# ShiftregisterTeil2.net
KiCad netlist of a schematic drawn in Altium Designer
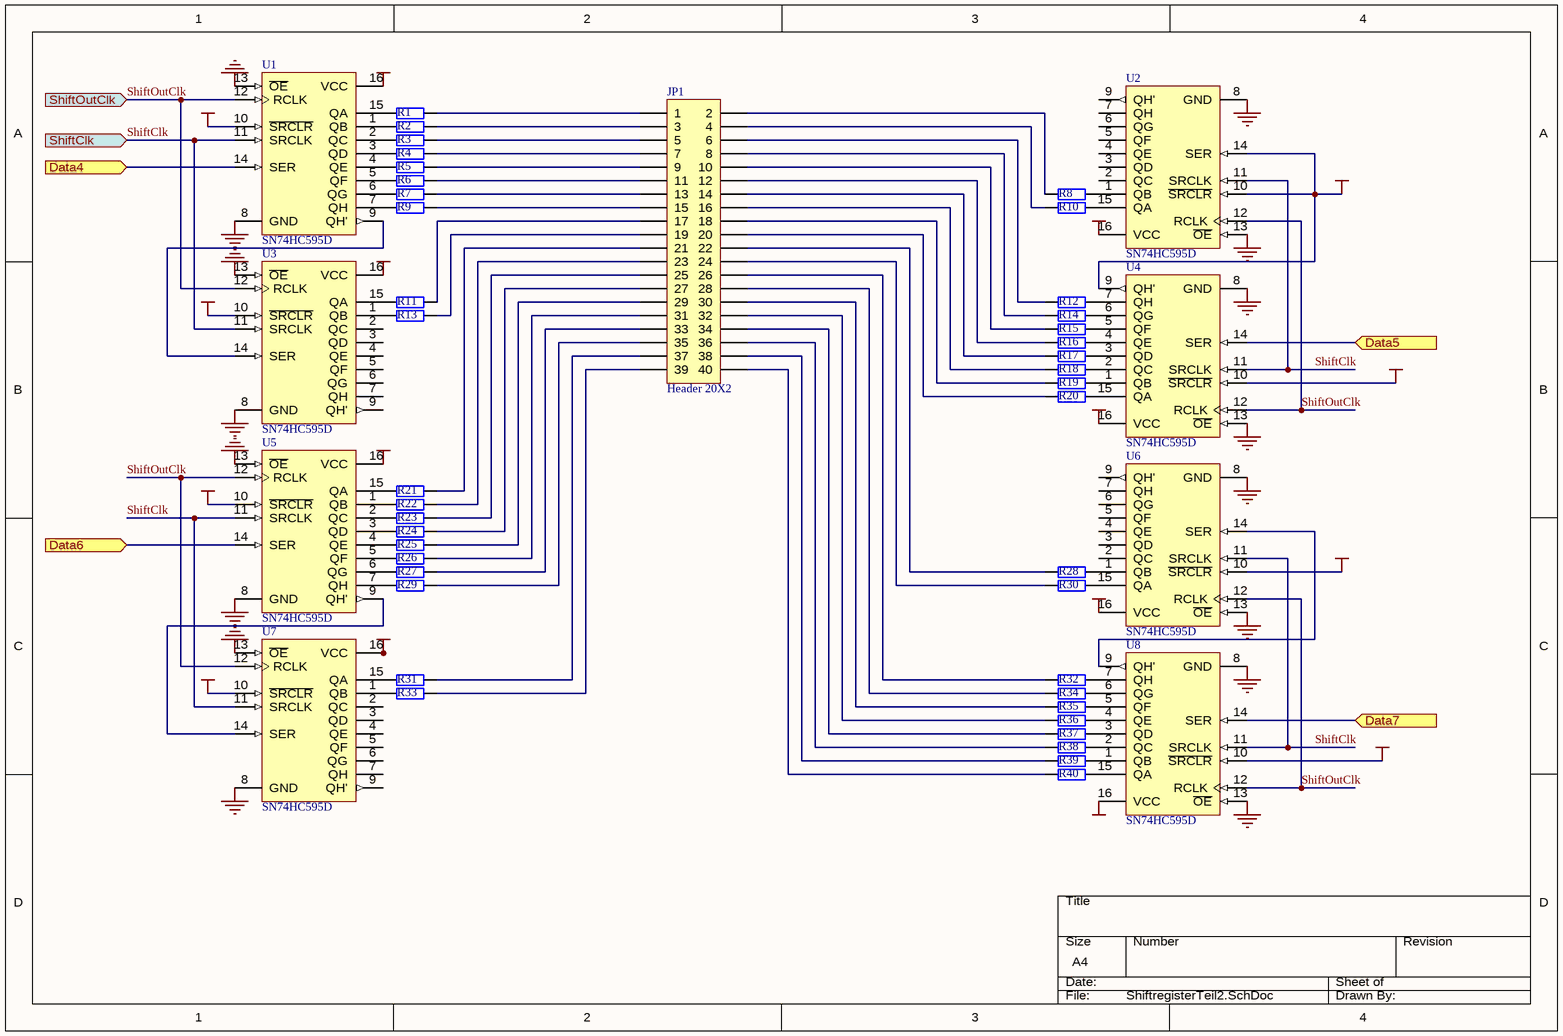
[diagram p0: ShiftregisterTeil2.SchDoc]

(export (version "E")
  (design (tool "Eeschema 10.0.6"))
  (components
    (comp (ref "JP1")
      (value "Header 20X2")
      (footprint "HDR2X20")
      (description "Header, 20-Pin, Dual row")
      (fields (field (name "PUBLISHER") "Altium Limited"))
      (libsource (lib "Miscellaneous Connectors") (part "Header 20X2"))
    )
    (comp (ref "R1")
      (value "~")
      (footprint "AXIAL-0.4")
      (description "Resistor")
      (fields (field (name "PUBLISHER") "Altium Limited"))
      (libsource (lib "Miscellaneous Devices") (part "Res2"))
    )
    (comp (ref "R2")
      (value "~")
      (footprint "AXIAL-0.4")
      (description "Resistor")
      (fields (field (name "PUBLISHER") "Altium Limited"))
      (libsource (lib "Miscellaneous Devices") (part "Res2"))
    )
    (comp (ref "R3")
      (value "~")
      (footprint "AXIAL-0.4")
      (description "Resistor")
      (fields (field (name "PUBLISHER") "Altium Limited"))
      (libsource (lib "Miscellaneous Devices") (part "Res2"))
    )
    (comp (ref "R4")
      (value "~")
      (footprint "AXIAL-0.4")
      (description "Resistor")
      (fields (field (name "PUBLISHER") "Altium Limited"))
      (libsource (lib "Miscellaneous Devices") (part "Res2"))
    )
    (comp (ref "R5")
      (value "~")
      (footprint "AXIAL-0.4")
      (description "Resistor")
      (fields (field (name "PUBLISHER") "Altium Limited"))
      (libsource (lib "Miscellaneous Devices") (part "Res2"))
    )
    (comp (ref "R6")
      (value "~")
      (footprint "AXIAL-0.4")
      (description "Resistor")
      (fields (field (name "PUBLISHER") "Altium Limited"))
      (libsource (lib "Miscellaneous Devices") (part "Res2"))
    )
    (comp (ref "R7")
      (value "~")
      (footprint "AXIAL-0.4")
      (description "Resistor")
      (fields (field (name "PUBLISHER") "Altium Limited"))
      (libsource (lib "Miscellaneous Devices") (part "Res2"))
    )
    (comp (ref "R8")
      (value "~")
      (footprint "AXIAL-0.4")
      (description "Resistor")
      (fields (field (name "PUBLISHER") "Altium Limited"))
      (libsource (lib "") (part "Res2_1"))
    )
    (comp (ref "R9")
      (value "~")
      (footprint "AXIAL-0.4")
      (description "Resistor")
      (fields (field (name "PUBLISHER") "Altium Limited"))
      (libsource (lib "Miscellaneous Devices") (part "Res2"))
    )
    (comp (ref "R10")
      (value "~")
      (footprint "AXIAL-0.4")
      (description "Resistor")
      (fields (field (name "PUBLISHER") "Altium Limited"))
      (libsource (lib "") (part "Res2_1"))
    )
    (comp (ref "R11")
      (value "~")
      (footprint "AXIAL-0.4")
      (description "Resistor")
      (fields (field (name "PUBLISHER") "Altium Limited"))
      (libsource (lib "Miscellaneous Devices") (part "Res2"))
    )
    (comp (ref "R12")
      (value "~")
      (footprint "AXIAL-0.4")
      (description "Resistor")
      (fields (field (name "PUBLISHER") "Altium Limited"))
      (libsource (lib "") (part "Res2_1"))
    )
    (comp (ref "R13")
      (value "~")
      (footprint "AXIAL-0.4")
      (description "Resistor")
      (fields (field (name "PUBLISHER") "Altium Limited"))
      (libsource (lib "Miscellaneous Devices") (part "Res2"))
    )
    (comp (ref "R14")
      (value "~")
      (footprint "AXIAL-0.4")
      (description "Resistor")
      (fields (field (name "PUBLISHER") "Altium Limited"))
      (libsource (lib "") (part "Res2_1"))
    )
    (comp (ref "R15")
      (value "~")
      (footprint "AXIAL-0.4")
      (description "Resistor")
      (fields (field (name "PUBLISHER") "Altium Limited"))
      (libsource (lib "") (part "Res2_1"))
    )
    (comp (ref "R16")
      (value "~")
      (footprint "AXIAL-0.4")
      (description "Resistor")
      (fields (field (name "PUBLISHER") "Altium Limited"))
      (libsource (lib "") (part "Res2_1"))
    )
    (comp (ref "R17")
      (value "~")
      (footprint "AXIAL-0.4")
      (description "Resistor")
      (fields (field (name "PUBLISHER") "Altium Limited"))
      (libsource (lib "") (part "Res2_1"))
    )
    (comp (ref "R18")
      (value "~")
      (footprint "AXIAL-0.4")
      (description "Resistor")
      (fields (field (name "PUBLISHER") "Altium Limited"))
      (libsource (lib "") (part "Res2_1"))
    )
    (comp (ref "R19")
      (value "~")
      (footprint "AXIAL-0.4")
      (description "Resistor")
      (fields (field (name "PUBLISHER") "Altium Limited"))
      (libsource (lib "") (part "Res2_1"))
    )
    (comp (ref "R20")
      (value "~")
      (footprint "AXIAL-0.4")
      (description "Resistor")
      (fields (field (name "PUBLISHER") "Altium Limited"))
      (libsource (lib "") (part "Res2_1"))
    )
    (comp (ref "R21")
      (value "~")
      (footprint "AXIAL-0.4")
      (description "Resistor")
      (fields (field (name "PUBLISHER") "Altium Limited"))
      (libsource (lib "Miscellaneous Devices") (part "Res2"))
    )
    (comp (ref "R22")
      (value "~")
      (footprint "AXIAL-0.4")
      (description "Resistor")
      (fields (field (name "PUBLISHER") "Altium Limited"))
      (libsource (lib "Miscellaneous Devices") (part "Res2"))
    )
    (comp (ref "R23")
      (value "~")
      (footprint "AXIAL-0.4")
      (description "Resistor")
      (fields (field (name "PUBLISHER") "Altium Limited"))
      (libsource (lib "Miscellaneous Devices") (part "Res2"))
    )
    (comp (ref "R24")
      (value "~")
      (footprint "AXIAL-0.4")
      (description "Resistor")
      (fields (field (name "PUBLISHER") "Altium Limited"))
      (libsource (lib "Miscellaneous Devices") (part "Res2"))
    )
    (comp (ref "R25")
      (value "~")
      (footprint "AXIAL-0.4")
      (description "Resistor")
      (fields (field (name "PUBLISHER") "Altium Limited"))
      (libsource (lib "Miscellaneous Devices") (part "Res2"))
    )
    (comp (ref "R26")
      (value "~")
      (footprint "AXIAL-0.4")
      (description "Resistor")
      (fields (field (name "PUBLISHER") "Altium Limited"))
      (libsource (lib "Miscellaneous Devices") (part "Res2"))
    )
    (comp (ref "R27")
      (value "~")
      (footprint "AXIAL-0.4")
      (description "Resistor")
      (fields (field (name "PUBLISHER") "Altium Limited"))
      (libsource (lib "Miscellaneous Devices") (part "Res2"))
    )
    (comp (ref "R28")
      (value "~")
      (footprint "AXIAL-0.4")
      (description "Resistor")
      (fields (field (name "PUBLISHER") "Altium Limited"))
      (libsource (lib "") (part "Res2_1"))
    )
    (comp (ref "R29")
      (value "~")
      (footprint "AXIAL-0.4")
      (description "Resistor")
      (fields (field (name "PUBLISHER") "Altium Limited"))
      (libsource (lib "Miscellaneous Devices") (part "Res2"))
    )
    (comp (ref "R30")
      (value "~")
      (footprint "AXIAL-0.4")
      (description "Resistor")
      (fields (field (name "PUBLISHER") "Altium Limited"))
      (libsource (lib "") (part "Res2_1"))
    )
    (comp (ref "R31")
      (value "~")
      (footprint "AXIAL-0.4")
      (description "Resistor")
      (fields (field (name "PUBLISHER") "Altium Limited"))
      (libsource (lib "Miscellaneous Devices") (part "Res2"))
    )
    (comp (ref "R32")
      (value "~")
      (footprint "AXIAL-0.4")
      (description "Resistor")
      (fields (field (name "PUBLISHER") "Altium Limited"))
      (libsource (lib "") (part "Res2_1"))
    )
    (comp (ref "R33")
      (value "~")
      (footprint "AXIAL-0.4")
      (description "Resistor")
      (fields (field (name "PUBLISHER") "Altium Limited"))
      (libsource (lib "Miscellaneous Devices") (part "Res2"))
    )
    (comp (ref "R34")
      (value "~")
      (footprint "AXIAL-0.4")
      (description "Resistor")
      (fields (field (name "PUBLISHER") "Altium Limited"))
      (libsource (lib "") (part "Res2_1"))
    )
    (comp (ref "R35")
      (value "~")
      (footprint "AXIAL-0.4")
      (description "Resistor")
      (fields (field (name "PUBLISHER") "Altium Limited"))
      (libsource (lib "") (part "Res2_1"))
    )
    (comp (ref "R36")
      (value "~")
      (footprint "AXIAL-0.4")
      (description "Resistor")
      (fields (field (name "PUBLISHER") "Altium Limited"))
      (libsource (lib "") (part "Res2_1"))
    )
    (comp (ref "R37")
      (value "~")
      (footprint "AXIAL-0.4")
      (description "Resistor")
      (fields (field (name "PUBLISHER") "Altium Limited"))
      (libsource (lib "") (part "Res2_1"))
    )
    (comp (ref "R38")
      (value "~")
      (footprint "AXIAL-0.4")
      (description "Resistor")
      (fields (field (name "PUBLISHER") "Altium Limited"))
      (libsource (lib "") (part "Res2_1"))
    )
    (comp (ref "R39")
      (value "~")
      (footprint "AXIAL-0.4")
      (description "Resistor")
      (fields (field (name "PUBLISHER") "Altium Limited"))
      (libsource (lib "") (part "Res2_1"))
    )
    (comp (ref "R40")
      (value "~")
      (footprint "AXIAL-0.4")
      (description "Resistor")
      (fields (field (name "PUBLISHER") "Altium Limited"))
      (libsource (lib "") (part "Res2_1"))
    )
    (comp (ref "U1")
      (value "SN74HC595D")
      (footprint "D016")
      (description "8-Bit Shift Register with 3-State Output Registers")
      (fields (field (name "PUBLISHER") "Altium Limited"))
      (libsource (lib "") (part "SN74HC595D_1"))
    )
    (comp (ref "U2")
      (value "SN74HC595D")
      (footprint "D016")
      (description "8-Bit Shift Register with 3-State Output Registers")
      (fields (field (name "PUBLISHER") "Altium Limited"))
      (libsource (lib "TI Logic Register") (part "SN74HC595D"))
    )
    (comp (ref "U3")
      (value "SN74HC595D")
      (footprint "D016")
      (description "8-Bit Shift Register with 3-State Output Registers")
      (fields (field (name "PUBLISHER") "Altium Limited"))
      (libsource (lib "") (part "SN74HC595D_1"))
    )
    (comp (ref "U4")
      (value "SN74HC595D")
      (footprint "D016")
      (description "8-Bit Shift Register with 3-State Output Registers")
      (fields (field (name "PUBLISHER") "Altium Limited"))
      (libsource (lib "TI Logic Register") (part "SN74HC595D"))
    )
    (comp (ref "U5")
      (value "SN74HC595D")
      (footprint "D016")
      (description "8-Bit Shift Register with 3-State Output Registers")
      (fields (field (name "PUBLISHER") "Altium Limited"))
      (libsource (lib "") (part "SN74HC595D_1"))
    )
    (comp (ref "U6")
      (value "SN74HC595D")
      (footprint "D016")
      (description "8-Bit Shift Register with 3-State Output Registers")
      (fields (field (name "PUBLISHER") "Altium Limited"))
      (libsource (lib "TI Logic Register") (part "SN74HC595D"))
    )
    (comp (ref "U7")
      (value "SN74HC595D")
      (footprint "D016")
      (description "8-Bit Shift Register with 3-State Output Registers")
      (fields (field (name "PUBLISHER") "Altium Limited"))
      (libsource (lib "") (part "SN74HC595D_1"))
    )
    (comp (ref "U8")
      (value "SN74HC595D")
      (footprint "D016")
      (description "8-Bit Shift Register with 3-State Output Registers")
      (fields (field (name "PUBLISHER") "Altium Limited"))
      (libsource (lib "TI Logic Register") (part "SN74HC595D"))
    )
  )
  (nets
    (net (code "1") (name "/Data4") (class "Default")
      (node (ref "U1") (pin "14") (pinfunction "SER_14") (pintype "input"))
    )
    (net (code "2") (name "/Data5") (class "Default")
      (node (ref "U4") (pin "14") (pinfunction "SER_14") (pintype "input"))
    )
    (net (code "3") (name "/Data6") (class "Default")
      (node (ref "U5") (pin "14") (pinfunction "SER_14") (pintype "input"))
    )
    (net (code "4") (name "/Data7") (class "Default")
      (node (ref "U8") (pin "14") (pinfunction "SER_14") (pintype "input"))
    )
    (net (code "5") (name "/ShiftClk") (class "Default")
      (node (ref "U1") (pin "11") (pinfunction "SRCLK_11") (pintype "input"))
      (node (ref "U2") (pin "11") (pinfunction "SRCLK_11") (pintype "input"))
      (node (ref "U3") (pin "11") (pinfunction "SRCLK_11") (pintype "input"))
      (node (ref "U4") (pin "11") (pinfunction "SRCLK_11") (pintype "input"))
      (node (ref "U5") (pin "11") (pinfunction "SRCLK_11") (pintype "input"))
      (node (ref "U6") (pin "11") (pinfunction "SRCLK_11") (pintype "input"))
      (node (ref "U7") (pin "11") (pinfunction "SRCLK_11") (pintype "input"))
      (node (ref "U8") (pin "11") (pinfunction "SRCLK_11") (pintype "input"))
    )
    (net (code "6") (name "/ShiftOutClk") (class "Default")
      (node (ref "U1") (pin "12") (pinfunction "RCLK_12") (pintype "input"))
      (node (ref "U2") (pin "12") (pinfunction "RCLK_12") (pintype "input"))
      (node (ref "U3") (pin "12") (pinfunction "RCLK_12") (pintype "input"))
      (node (ref "U4") (pin "12") (pinfunction "RCLK_12") (pintype "input"))
      (node (ref "U5") (pin "12") (pinfunction "RCLK_12") (pintype "input"))
      (node (ref "U6") (pin "12") (pinfunction "RCLK_12") (pintype "input"))
      (node (ref "U7") (pin "12") (pinfunction "RCLK_12") (pintype "input"))
      (node (ref "U8") (pin "12") (pinfunction "RCLK_12") (pintype "input"))
    )
    (net (code "7") (name "GND") (class "Default")
      (node (ref "U1") (pin "13") (pinfunction "~{OE}_13") (pintype "input"))
      (node (ref "U1") (pin "8") (pinfunction "GND_8") (pintype "power_in"))
      (node (ref "U2") (pin "13") (pinfunction "~{OE}_13") (pintype "input"))
      (node (ref "U2") (pin "8") (pinfunction "GND_8") (pintype "power_in"))
      (node (ref "U3") (pin "13") (pinfunction "~{OE}_13") (pintype "input"))
      (node (ref "U3") (pin "8") (pinfunction "GND_8") (pintype "power_in"))
      (node (ref "U4") (pin "13") (pinfunction "~{OE}_13") (pintype "input"))
      (node (ref "U4") (pin "8") (pinfunction "GND_8") (pintype "power_in"))
      (node (ref "U5") (pin "13") (pinfunction "~{OE}_13") (pintype "input"))
      (node (ref "U5") (pin "8") (pinfunction "GND_8") (pintype "power_in"))
      (node (ref "U6") (pin "13") (pinfunction "~{OE}_13") (pintype "input"))
      (node (ref "U6") (pin "8") (pinfunction "GND_8") (pintype "power_in"))
      (node (ref "U7") (pin "13") (pinfunction "~{OE}_13") (pintype "input"))
      (node (ref "U7") (pin "8") (pinfunction "GND_8") (pintype "power_in"))
      (node (ref "U8") (pin "13") (pinfunction "~{OE}_13") (pintype "input"))
      (node (ref "U8") (pin "8") (pinfunction "GND_8") (pintype "power_in"))
    )
    (net (code "8") (name "Net-(JP1-Pad1)") (class "Default")
      (node (ref "JP1") (pin "1") (pinfunction "1_1") (pintype "passive"))
      (node (ref "R1") (pin "2") (pinfunction "2_2") (pintype "passive"))
    )
    (net (code "9") (name "Net-(JP1-Pad2)") (class "Default")
      (node (ref "JP1") (pin "2") (pinfunction "2_2") (pintype "passive"))
      (node (ref "R8") (pin "2") (pinfunction "2_2") (pintype "passive"))
    )
    (net (code "10") (name "Net-(JP1-Pad3)") (class "Default")
      (node (ref "JP1") (pin "3") (pinfunction "3_3") (pintype "passive"))
      (node (ref "R2") (pin "2") (pinfunction "2_2") (pintype "passive"))
    )
    (net (code "11") (name "Net-(JP1-Pad4)") (class "Default")
      (node (ref "JP1") (pin "4") (pinfunction "4_4") (pintype "passive"))
      (node (ref "R10") (pin "2") (pinfunction "2_2") (pintype "passive"))
    )
    (net (code "12") (name "Net-(JP1-Pad5)") (class "Default")
      (node (ref "JP1") (pin "5") (pinfunction "5_5") (pintype "passive"))
      (node (ref "R3") (pin "2") (pinfunction "2_2") (pintype "passive"))
    )
    (net (code "13") (name "Net-(JP1-Pad6)") (class "Default")
      (node (ref "JP1") (pin "6") (pinfunction "6_6") (pintype "passive"))
      (node (ref "R12") (pin "2") (pinfunction "2_2") (pintype "passive"))
    )
    (net (code "14") (name "Net-(JP1-Pad7)") (class "Default")
      (node (ref "JP1") (pin "7") (pinfunction "7_7") (pintype "passive"))
      (node (ref "R4") (pin "2") (pinfunction "2_2") (pintype "passive"))
    )
    (net (code "15") (name "Net-(JP1-Pad8)") (class "Default")
      (node (ref "JP1") (pin "8") (pinfunction "8_8") (pintype "passive"))
      (node (ref "R14") (pin "2") (pinfunction "2_2") (pintype "passive"))
    )
    (net (code "16") (name "Net-(JP1-Pad9)") (class "Default")
      (node (ref "JP1") (pin "9") (pinfunction "9_9") (pintype "passive"))
      (node (ref "R5") (pin "2") (pinfunction "2_2") (pintype "passive"))
    )
    (net (code "17") (name "Net-(JP1-Pad10)") (class "Default")
      (node (ref "JP1") (pin "10") (pinfunction "10_10") (pintype "passive"))
      (node (ref "R15") (pin "2") (pinfunction "2_2") (pintype "passive"))
    )
    (net (code "18") (name "Net-(JP1-Pad11)") (class "Default")
      (node (ref "JP1") (pin "11") (pinfunction "11_11") (pintype "passive"))
      (node (ref "R6") (pin "2") (pinfunction "2_2") (pintype "passive"))
    )
    (net (code "19") (name "Net-(JP1-Pad12)") (class "Default")
      (node (ref "JP1") (pin "12") (pinfunction "12_12") (pintype "passive"))
      (node (ref "R16") (pin "2") (pinfunction "2_2") (pintype "passive"))
    )
    (net (code "20") (name "Net-(JP1-Pad13)") (class "Default")
      (node (ref "JP1") (pin "13") (pinfunction "13_13") (pintype "passive"))
      (node (ref "R7") (pin "2") (pinfunction "2_2") (pintype "passive"))
    )
    (net (code "21") (name "Net-(JP1-Pad14)") (class "Default")
      (node (ref "JP1") (pin "14") (pinfunction "14_14") (pintype "passive"))
      (node (ref "R17") (pin "2") (pinfunction "2_2") (pintype "passive"))
    )
    (net (code "22") (name "Net-(JP1-Pad15)") (class "Default")
      (node (ref "JP1") (pin "15") (pinfunction "15_15") (pintype "passive"))
      (node (ref "R9") (pin "2") (pinfunction "2_2") (pintype "passive"))
    )
    (net (code "23") (name "Net-(JP1-Pad16)") (class "Default")
      (node (ref "JP1") (pin "16") (pinfunction "16_16") (pintype "passive"))
      (node (ref "R18") (pin "2") (pinfunction "2_2") (pintype "passive"))
    )
    (net (code "24") (name "Net-(JP1-Pad17)") (class "Default")
      (node (ref "JP1") (pin "17") (pinfunction "17_17") (pintype "passive"))
      (node (ref "R11") (pin "2") (pinfunction "2_2") (pintype "passive"))
    )
    (net (code "25") (name "Net-(JP1-Pad18)") (class "Default")
      (node (ref "JP1") (pin "18") (pinfunction "18_18") (pintype "passive"))
      (node (ref "R19") (pin "2") (pinfunction "2_2") (pintype "passive"))
    )
    (net (code "26") (name "Net-(JP1-Pad19)") (class "Default")
      (node (ref "JP1") (pin "19") (pinfunction "19_19") (pintype "passive"))
      (node (ref "R13") (pin "2") (pinfunction "2_2") (pintype "passive"))
    )
    (net (code "27") (name "Net-(JP1-Pad20)") (class "Default")
      (node (ref "JP1") (pin "20") (pinfunction "20_20") (pintype "passive"))
      (node (ref "R20") (pin "2") (pinfunction "2_2") (pintype "passive"))
    )
    (net (code "28") (name "Net-(JP1-Pad21)") (class "Default")
      (node (ref "JP1") (pin "21") (pinfunction "21_21") (pintype "passive"))
      (node (ref "R21") (pin "2") (pinfunction "2_2") (pintype "passive"))
    )
    (net (code "29") (name "Net-(JP1-Pad22)") (class "Default")
      (node (ref "JP1") (pin "22") (pinfunction "22_22") (pintype "passive"))
      (node (ref "R28") (pin "2") (pinfunction "2_2") (pintype "passive"))
    )
    (net (code "30") (name "Net-(JP1-Pad23)") (class "Default")
      (node (ref "JP1") (pin "23") (pinfunction "23_23") (pintype "passive"))
      (node (ref "R22") (pin "2") (pinfunction "2_2") (pintype "passive"))
    )
    (net (code "31") (name "Net-(JP1-Pad24)") (class "Default")
      (node (ref "JP1") (pin "24") (pinfunction "24_24") (pintype "passive"))
      (node (ref "R30") (pin "2") (pinfunction "2_2") (pintype "passive"))
    )
    (net (code "32") (name "Net-(JP1-Pad25)") (class "Default")
      (node (ref "JP1") (pin "25") (pinfunction "25_25") (pintype "passive"))
      (node (ref "R23") (pin "2") (pinfunction "2_2") (pintype "passive"))
    )
    (net (code "33") (name "Net-(JP1-Pad26)") (class "Default")
      (node (ref "JP1") (pin "26") (pinfunction "26_26") (pintype "passive"))
      (node (ref "R32") (pin "2") (pinfunction "2_2") (pintype "passive"))
    )
    (net (code "34") (name "Net-(JP1-Pad27)") (class "Default")
      (node (ref "JP1") (pin "27") (pinfunction "27_27") (pintype "passive"))
      (node (ref "R24") (pin "2") (pinfunction "2_2") (pintype "passive"))
    )
    (net (code "35") (name "Net-(JP1-Pad28)") (class "Default")
      (node (ref "JP1") (pin "28") (pinfunction "28_28") (pintype "passive"))
      (node (ref "R34") (pin "2") (pinfunction "2_2") (pintype "passive"))
    )
    (net (code "36") (name "Net-(JP1-Pad29)") (class "Default")
      (node (ref "JP1") (pin "29") (pinfunction "29_29") (pintype "passive"))
      (node (ref "R25") (pin "2") (pinfunction "2_2") (pintype "passive"))
    )
    (net (code "37") (name "Net-(JP1-Pad30)") (class "Default")
      (node (ref "JP1") (pin "30") (pinfunction "30_30") (pintype "passive"))
      (node (ref "R35") (pin "2") (pinfunction "2_2") (pintype "passive"))
    )
    (net (code "38") (name "Net-(JP1-Pad31)") (class "Default")
      (node (ref "JP1") (pin "31") (pinfunction "31_31") (pintype "passive"))
      (node (ref "R26") (pin "2") (pinfunction "2_2") (pintype "passive"))
    )
    (net (code "39") (name "Net-(JP1-Pad32)") (class "Default")
      (node (ref "JP1") (pin "32") (pinfunction "32_32") (pintype "passive"))
      (node (ref "R36") (pin "2") (pinfunction "2_2") (pintype "passive"))
    )
    (net (code "40") (name "Net-(JP1-Pad33)") (class "Default")
      (node (ref "JP1") (pin "33") (pinfunction "33_33") (pintype "passive"))
      (node (ref "R27") (pin "2") (pinfunction "2_2") (pintype "passive"))
    )
    (net (code "41") (name "Net-(JP1-Pad34)") (class "Default")
      (node (ref "JP1") (pin "34") (pinfunction "34_34") (pintype "passive"))
      (node (ref "R37") (pin "2") (pinfunction "2_2") (pintype "passive"))
    )
    (net (code "42") (name "Net-(JP1-Pad35)") (class "Default")
      (node (ref "JP1") (pin "35") (pinfunction "35_35") (pintype "passive"))
      (node (ref "R29") (pin "2") (pinfunction "2_2") (pintype "passive"))
    )
    (net (code "43") (name "Net-(JP1-Pad36)") (class "Default")
      (node (ref "JP1") (pin "36") (pinfunction "36_36") (pintype "passive"))
      (node (ref "R38") (pin "2") (pinfunction "2_2") (pintype "passive"))
    )
    (net (code "44") (name "Net-(JP1-Pad37)") (class "Default")
      (node (ref "JP1") (pin "37") (pinfunction "37_37") (pintype "passive"))
      (node (ref "R31") (pin "2") (pinfunction "2_2") (pintype "passive"))
    )
    (net (code "45") (name "Net-(JP1-Pad38)") (class "Default")
      (node (ref "JP1") (pin "38") (pinfunction "38_38") (pintype "passive"))
      (node (ref "R39") (pin "2") (pinfunction "2_2") (pintype "passive"))
    )
    (net (code "46") (name "Net-(JP1-Pad39)") (class "Default")
      (node (ref "JP1") (pin "39") (pinfunction "39_39") (pintype "passive"))
      (node (ref "R33") (pin "2") (pinfunction "2_2") (pintype "passive"))
    )
    (net (code "47") (name "Net-(JP1-Pad40)") (class "Default")
      (node (ref "JP1") (pin "40") (pinfunction "40_40") (pintype "passive"))
      (node (ref "R40") (pin "2") (pinfunction "2_2") (pintype "passive"))
    )
    (net (code "48") (name "Net-(U1-QA)") (class "Default")
      (node (ref "R1") (pin "1") (pinfunction "1_1") (pintype "passive"))
      (node (ref "U1") (pin "15") (pinfunction "QA_15") (pintype "tri_state"))
    )
    (net (code "49") (name "Net-(U1-QB)") (class "Default")
      (node (ref "R2") (pin "1") (pinfunction "1_1") (pintype "passive"))
      (node (ref "U1") (pin "1") (pinfunction "QB_1") (pintype "tri_state"))
    )
    (net (code "50") (name "Net-(U1-QC)") (class "Default")
      (node (ref "R3") (pin "1") (pinfunction "1_1") (pintype "passive"))
      (node (ref "U1") (pin "2") (pinfunction "QC_2") (pintype "tri_state"))
    )
    (net (code "51") (name "Net-(U1-QD)") (class "Default")
      (node (ref "R4") (pin "1") (pinfunction "1_1") (pintype "passive"))
      (node (ref "U1") (pin "3") (pinfunction "QD_3") (pintype "tri_state"))
    )
    (net (code "52") (name "Net-(U1-QE)") (class "Default")
      (node (ref "R5") (pin "1") (pinfunction "1_1") (pintype "passive"))
      (node (ref "U1") (pin "4") (pinfunction "QE_4") (pintype "tri_state"))
    )
    (net (code "53") (name "Net-(U1-QF)") (class "Default")
      (node (ref "R6") (pin "1") (pinfunction "1_1") (pintype "passive"))
      (node (ref "U1") (pin "5") (pinfunction "QF_5") (pintype "tri_state"))
    )
    (net (code "54") (name "Net-(U1-QG)") (class "Default")
      (node (ref "R7") (pin "1") (pinfunction "1_1") (pintype "passive"))
      (node (ref "U1") (pin "6") (pinfunction "QG_6") (pintype "tri_state"))
    )
    (net (code "55") (name "Net-(U1-QH')") (class "Default")
      (node (ref "U1") (pin "9") (pinfunction "QH'_9") (pintype "output"))
      (node (ref "U3") (pin "14") (pinfunction "SER_14") (pintype "input"))
    )
    (net (code "56") (name "Net-(U1-QH)") (class "Default")
      (node (ref "R9") (pin "1") (pinfunction "1_1") (pintype "passive"))
      (node (ref "U1") (pin "7") (pinfunction "QH_7") (pintype "tri_state"))
    )
    (net (code "57") (name "Net-(U2-QA)") (class "Default")
      (node (ref "R10") (pin "1") (pinfunction "1_1") (pintype "passive"))
      (node (ref "U2") (pin "15") (pinfunction "QA_15") (pintype "tri_state"))
    )
    (net (code "58") (name "Net-(U2-QB)") (class "Default")
      (node (ref "R8") (pin "1") (pinfunction "1_1") (pintype "passive"))
      (node (ref "U2") (pin "1") (pinfunction "QB_1") (pintype "tri_state"))
    )
    (net (code "59") (name "Net-(U3-QA)") (class "Default")
      (node (ref "R11") (pin "1") (pinfunction "1_1") (pintype "passive"))
      (node (ref "U3") (pin "15") (pinfunction "QA_15") (pintype "tri_state"))
    )
    (net (code "60") (name "Net-(U3-QB)") (class "Default")
      (node (ref "R13") (pin "1") (pinfunction "1_1") (pintype "passive"))
      (node (ref "U3") (pin "1") (pinfunction "QB_1") (pintype "tri_state"))
    )
    (net (code "61") (name "Net-(U4-QA)") (class "Default")
      (node (ref "R20") (pin "1") (pinfunction "1_1") (pintype "passive"))
      (node (ref "U4") (pin "15") (pinfunction "QA_15") (pintype "tri_state"))
    )
    (net (code "62") (name "Net-(U4-QB)") (class "Default")
      (node (ref "R19") (pin "1") (pinfunction "1_1") (pintype "passive"))
      (node (ref "U4") (pin "1") (pinfunction "QB_1") (pintype "tri_state"))
    )
    (net (code "63") (name "Net-(U4-QC)") (class "Default")
      (node (ref "R18") (pin "1") (pinfunction "1_1") (pintype "passive"))
      (node (ref "U4") (pin "2") (pinfunction "QC_2") (pintype "tri_state"))
    )
    (net (code "64") (name "Net-(U4-QD)") (class "Default")
      (node (ref "R17") (pin "1") (pinfunction "1_1") (pintype "passive"))
      (node (ref "U4") (pin "3") (pinfunction "QD_3") (pintype "tri_state"))
    )
    (net (code "65") (name "Net-(U4-QE)") (class "Default")
      (node (ref "R16") (pin "1") (pinfunction "1_1") (pintype "passive"))
      (node (ref "U4") (pin "4") (pinfunction "QE_4") (pintype "tri_state"))
    )
    (net (code "66") (name "Net-(U4-QF)") (class "Default")
      (node (ref "R15") (pin "1") (pinfunction "1_1") (pintype "passive"))
      (node (ref "U4") (pin "5") (pinfunction "QF_5") (pintype "tri_state"))
    )
    (net (code "67") (name "Net-(U4-QG)") (class "Default")
      (node (ref "R14") (pin "1") (pinfunction "1_1") (pintype "passive"))
      (node (ref "U4") (pin "6") (pinfunction "QG_6") (pintype "tri_state"))
    )
    (net (code "68") (name "Net-(U4-QH)") (class "Default")
      (node (ref "R12") (pin "1") (pinfunction "1_1") (pintype "passive"))
      (node (ref "U4") (pin "7") (pinfunction "QH_7") (pintype "tri_state"))
    )
    (net (code "69") (name "Net-(U5-QA)") (class "Default")
      (node (ref "R21") (pin "1") (pinfunction "1_1") (pintype "passive"))
      (node (ref "U5") (pin "15") (pinfunction "QA_15") (pintype "tri_state"))
    )
    (net (code "70") (name "Net-(U5-QB)") (class "Default")
      (node (ref "R22") (pin "1") (pinfunction "1_1") (pintype "passive"))
      (node (ref "U5") (pin "1") (pinfunction "QB_1") (pintype "tri_state"))
    )
    (net (code "71") (name "Net-(U5-QC)") (class "Default")
      (node (ref "R23") (pin "1") (pinfunction "1_1") (pintype "passive"))
      (node (ref "U5") (pin "2") (pinfunction "QC_2") (pintype "tri_state"))
    )
    (net (code "72") (name "Net-(U5-QD)") (class "Default")
      (node (ref "R24") (pin "1") (pinfunction "1_1") (pintype "passive"))
      (node (ref "U5") (pin "3") (pinfunction "QD_3") (pintype "tri_state"))
    )
    (net (code "73") (name "Net-(U5-QE)") (class "Default")
      (node (ref "R25") (pin "1") (pinfunction "1_1") (pintype "passive"))
      (node (ref "U5") (pin "4") (pinfunction "QE_4") (pintype "tri_state"))
    )
    (net (code "74") (name "Net-(U5-QF)") (class "Default")
      (node (ref "R26") (pin "1") (pinfunction "1_1") (pintype "passive"))
      (node (ref "U5") (pin "5") (pinfunction "QF_5") (pintype "tri_state"))
    )
    (net (code "75") (name "Net-(U5-QG)") (class "Default")
      (node (ref "R27") (pin "1") (pinfunction "1_1") (pintype "passive"))
      (node (ref "U5") (pin "6") (pinfunction "QG_6") (pintype "tri_state"))
    )
    (net (code "76") (name "Net-(U5-QH')") (class "Default")
      (node (ref "U5") (pin "9") (pinfunction "QH'_9") (pintype "output"))
      (node (ref "U7") (pin "14") (pinfunction "SER_14") (pintype "input"))
    )
    (net (code "77") (name "Net-(U5-QH)") (class "Default")
      (node (ref "R29") (pin "1") (pinfunction "1_1") (pintype "passive"))
      (node (ref "U5") (pin "7") (pinfunction "QH_7") (pintype "tri_state"))
    )
    (net (code "78") (name "Net-(U6-QA)") (class "Default")
      (node (ref "R30") (pin "1") (pinfunction "1_1") (pintype "passive"))
      (node (ref "U6") (pin "15") (pinfunction "QA_15") (pintype "tri_state"))
    )
    (net (code "79") (name "Net-(U6-QB)") (class "Default")
      (node (ref "R28") (pin "1") (pinfunction "1_1") (pintype "passive"))
      (node (ref "U6") (pin "1") (pinfunction "QB_1") (pintype "tri_state"))
    )
    (net (code "80") (name "Net-(U6-SER)") (class "Default")
      (node (ref "U6") (pin "14") (pinfunction "SER_14") (pintype "input"))
      (node (ref "U8") (pin "9") (pinfunction "QH'_9") (pintype "output"))
    )
    (net (code "81") (name "Net-(U7-QA)") (class "Default")
      (node (ref "R31") (pin "1") (pinfunction "1_1") (pintype "passive"))
      (node (ref "U7") (pin "15") (pinfunction "QA_15") (pintype "tri_state"))
    )
    (net (code "82") (name "Net-(U7-QB)") (class "Default")
      (node (ref "R33") (pin "1") (pinfunction "1_1") (pintype "passive"))
      (node (ref "U7") (pin "1") (pinfunction "QB_1") (pintype "tri_state"))
    )
    (net (code "83") (name "Net-(U8-QA)") (class "Default")
      (node (ref "R40") (pin "1") (pinfunction "1_1") (pintype "passive"))
      (node (ref "U8") (pin "15") (pinfunction "QA_15") (pintype "tri_state"))
    )
    (net (code "84") (name "Net-(U8-QB)") (class "Default")
      (node (ref "R39") (pin "1") (pinfunction "1_1") (pintype "passive"))
      (node (ref "U8") (pin "1") (pinfunction "QB_1") (pintype "tri_state"))
    )
    (net (code "85") (name "Net-(U8-QC)") (class "Default")
      (node (ref "R38") (pin "1") (pinfunction "1_1") (pintype "passive"))
      (node (ref "U8") (pin "2") (pinfunction "QC_2") (pintype "tri_state"))
    )
    (net (code "86") (name "Net-(U8-QD)") (class "Default")
      (node (ref "R37") (pin "1") (pinfunction "1_1") (pintype "passive"))
      (node (ref "U8") (pin "3") (pinfunction "QD_3") (pintype "tri_state"))
    )
    (net (code "87") (name "Net-(U8-QE)") (class "Default")
      (node (ref "R36") (pin "1") (pinfunction "1_1") (pintype "passive"))
      (node (ref "U8") (pin "4") (pinfunction "QE_4") (pintype "tri_state"))
    )
    (net (code "88") (name "Net-(U8-QF)") (class "Default")
      (node (ref "R35") (pin "1") (pinfunction "1_1") (pintype "passive"))
      (node (ref "U8") (pin "5") (pinfunction "QF_5") (pintype "tri_state"))
    )
    (net (code "89") (name "Net-(U8-QG)") (class "Default")
      (node (ref "R34") (pin "1") (pinfunction "1_1") (pintype "passive"))
      (node (ref "U8") (pin "6") (pinfunction "QG_6") (pintype "tri_state"))
    )
    (net (code "90") (name "Net-(U8-QH)") (class "Default")
      (node (ref "R32") (pin "1") (pinfunction "1_1") (pintype "passive"))
      (node (ref "U8") (pin "7") (pinfunction "QH_7") (pintype "tri_state"))
    )
    (net (code "91") (name "VCC") (class "Default")
      (node (ref "U1") (pin "10") (pinfunction "~{SRCLR}_10") (pintype "input"))
      (node (ref "U1") (pin "16") (pinfunction "VCC_16") (pintype "power_in"))
      (node (ref "U2") (pin "10") (pinfunction "~{SRCLR}_10") (pintype "input"))
      (node (ref "U2") (pin "14") (pinfunction "SER_14") (pintype "input"))
      (node (ref "U2") (pin "16") (pinfunction "VCC_16") (pintype "power_in"))
      (node (ref "U3") (pin "10") (pinfunction "~{SRCLR}_10") (pintype "input"))
      (node (ref "U3") (pin "16") (pinfunction "VCC_16") (pintype "power_in"))
      (node (ref "U4") (pin "10") (pinfunction "~{SRCLR}_10") (pintype "input"))
      (node (ref "U4") (pin "16") (pinfunction "VCC_16") (pintype "power_in"))
      (node (ref "U4") (pin "9") (pinfunction "QH'_9") (pintype "output"))
      (node (ref "U5") (pin "10") (pinfunction "~{SRCLR}_10") (pintype "input"))
      (node (ref "U5") (pin "16") (pinfunction "VCC_16") (pintype "power_in"))
      (node (ref "U6") (pin "10") (pinfunction "~{SRCLR}_10") (pintype "input"))
      (node (ref "U6") (pin "16") (pinfunction "VCC_16") (pintype "power_in"))
      (node (ref "U7") (pin "10") (pinfunction "~{SRCLR}_10") (pintype "input"))
      (node (ref "U7") (pin "16") (pinfunction "VCC_16") (pintype "power_in"))
      (node (ref "U8") (pin "10") (pinfunction "~{SRCLR}_10") (pintype "input"))
      (node (ref "U8") (pin "16") (pinfunction "VCC_16") (pintype "power_in"))
    )
    (net (code "92") (name "unconnected-(U2-QC-Pad2)") (class "Default")
      (node (ref "U2") (pin "2") (pinfunction "QC_2") (pintype "tri_state"))
    )
    (net (code "93") (name "unconnected-(U2-QD-Pad3)") (class "Default")
      (node (ref "U2") (pin "3") (pinfunction "QD_3") (pintype "tri_state"))
    )
    (net (code "94") (name "unconnected-(U2-QE-Pad4)") (class "Default")
      (node (ref "U2") (pin "4") (pinfunction "QE_4") (pintype "tri_state"))
    )
    (net (code "95") (name "unconnected-(U2-QF-Pad5)") (class "Default")
      (node (ref "U2") (pin "5") (pinfunction "QF_5") (pintype "tri_state"))
    )
    (net (code "96") (name "unconnected-(U2-QG-Pad6)") (class "Default")
      (node (ref "U2") (pin "6") (pinfunction "QG_6") (pintype "tri_state"))
    )
    (net (code "97") (name "unconnected-(U2-QH'-Pad9)") (class "Default")
      (node (ref "U2") (pin "9") (pinfunction "QH'_9") (pintype "output"))
    )
    (net (code "98") (name "unconnected-(U2-QH-Pad7)") (class "Default")
      (node (ref "U2") (pin "7") (pinfunction "QH_7") (pintype "tri_state"))
    )
    (net (code "99") (name "unconnected-(U3-QC-Pad2)") (class "Default")
      (node (ref "U3") (pin "2") (pinfunction "QC_2") (pintype "tri_state"))
    )
    (net (code "100") (name "unconnected-(U3-QD-Pad3)") (class "Default")
      (node (ref "U3") (pin "3") (pinfunction "QD_3") (pintype "tri_state"))
    )
    (net (code "101") (name "unconnected-(U3-QE-Pad4)") (class "Default")
      (node (ref "U3") (pin "4") (pinfunction "QE_4") (pintype "tri_state"))
    )
    (net (code "102") (name "unconnected-(U3-QF-Pad5)") (class "Default")
      (node (ref "U3") (pin "5") (pinfunction "QF_5") (pintype "tri_state"))
    )
    (net (code "103") (name "unconnected-(U3-QG-Pad6)") (class "Default")
      (node (ref "U3") (pin "6") (pinfunction "QG_6") (pintype "tri_state"))
    )
    (net (code "104") (name "unconnected-(U3-QH'-Pad9)") (class "Default")
      (node (ref "U3") (pin "9") (pinfunction "QH'_9") (pintype "output"))
    )
    (net (code "105") (name "unconnected-(U3-QH-Pad7)") (class "Default")
      (node (ref "U3") (pin "7") (pinfunction "QH_7") (pintype "tri_state"))
    )
    (net (code "106") (name "unconnected-(U6-QC-Pad2)") (class "Default")
      (node (ref "U6") (pin "2") (pinfunction "QC_2") (pintype "tri_state"))
    )
    (net (code "107") (name "unconnected-(U6-QD-Pad3)") (class "Default")
      (node (ref "U6") (pin "3") (pinfunction "QD_3") (pintype "tri_state"))
    )
    (net (code "108") (name "unconnected-(U6-QE-Pad4)") (class "Default")
      (node (ref "U6") (pin "4") (pinfunction "QE_4") (pintype "tri_state"))
    )
    (net (code "109") (name "unconnected-(U6-QF-Pad5)") (class "Default")
      (node (ref "U6") (pin "5") (pinfunction "QF_5") (pintype "tri_state"))
    )
    (net (code "110") (name "unconnected-(U6-QG-Pad6)") (class "Default")
      (node (ref "U6") (pin "6") (pinfunction "QG_6") (pintype "tri_state"))
    )
    (net (code "111") (name "unconnected-(U6-QH'-Pad9)") (class "Default")
      (node (ref "U6") (pin "9") (pinfunction "QH'_9") (pintype "output"))
    )
    (net (code "112") (name "unconnected-(U6-QH-Pad7)") (class "Default")
      (node (ref "U6") (pin "7") (pinfunction "QH_7") (pintype "tri_state"))
    )
    (net (code "113") (name "unconnected-(U7-QC-Pad2)") (class "Default")
      (node (ref "U7") (pin "2") (pinfunction "QC_2") (pintype "tri_state"))
    )
    (net (code "114") (name "unconnected-(U7-QD-Pad3)") (class "Default")
      (node (ref "U7") (pin "3") (pinfunction "QD_3") (pintype "tri_state"))
    )
    (net (code "115") (name "unconnected-(U7-QE-Pad4)") (class "Default")
      (node (ref "U7") (pin "4") (pinfunction "QE_4") (pintype "tri_state"))
    )
    (net (code "116") (name "unconnected-(U7-QF-Pad5)") (class "Default")
      (node (ref "U7") (pin "5") (pinfunction "QF_5") (pintype "tri_state"))
    )
    (net (code "117") (name "unconnected-(U7-QG-Pad6)") (class "Default")
      (node (ref "U7") (pin "6") (pinfunction "QG_6") (pintype "tri_state"))
    )
    (net (code "118") (name "unconnected-(U7-QH'-Pad9)") (class "Default")
      (node (ref "U7") (pin "9") (pinfunction "QH'_9") (pintype "output"))
    )
    (net (code "119") (name "unconnected-(U7-QH-Pad7)") (class "Default")
      (node (ref "U7") (pin "7") (pinfunction "QH_7") (pintype "tri_state"))
    )
  )
)
